# Better_Flasher.net
KiCad netlist of a schematic drawn in EAGLE
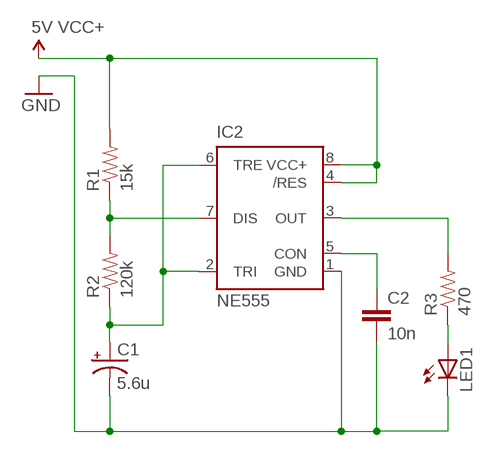
[diagram p0: schematic, sheet 1]

(export (version "E")
  (design (tool "Eeschema 10.0.6"))
  (components
    (comp (ref "C1")
      (value "5.6u")
      (footprint "eagle-import:CPOL-RADIAL-10UF-25V")
      (libsource (lib "eagle-import") (part "CAP_POLPTH2"))
    )
    (comp (ref "C2")
      (value "10n")
      (footprint "eagle-import:CAP-PTH-SMALL")
      (libsource (lib "eagle-import") (part "CAPPTH"))
    )
    (comp (ref "IC2")
      (value "NE555")
      (footprint "eagle-import:DIL-08")
      (fields (field (name "MF") "Arrow Electronics") (field (name "MPN") "NE555N"))
      (libsource (lib "eagle-import") (part "NE555"))
    )
    (comp (ref "LED1")
      (value "LED5MM")
      (footprint "eagle-import:LED5MM")
      (libsource (lib "eagle-import") (part "LED5MM"))
    )
    (comp (ref "R1")
      (value "15k")
      (footprint "eagle-import:AXIAL-0.3")
      (libsource (lib "eagle-import") (part "RESISTORAXIAL-0.3"))
    )
    (comp (ref "R2")
      (value "120k")
      (footprint "eagle-import:AXIAL-0.3")
      (libsource (lib "eagle-import") (part "RESISTORAXIAL-0.3"))
    )
    (comp (ref "R3")
      (value "470")
      (footprint "eagle-import:AXIAL-0.3")
      (libsource (lib "eagle-import") (part "RESISTORAXIAL-0.3"))
    )
  )
  (nets
    (net (code "1") (name "5V VCC+") (class "Default")
      (node (ref "IC2") (pin "4") (pinfunction "/RES_4") (pintype "input"))
      (node (ref "IC2") (pin "8") (pinfunction "VCC+_8") (pintype "power_in"))
      (node (ref "R1") (pin "P$2") (pinfunction "2_P$2") (pintype "passive"))
    )
    (net (code "2") (name "GND") (class "Default")
      (node (ref "C1") (pin "2") (pinfunction "-_2") (pintype "passive"))
      (node (ref "C2") (pin "2") (pinfunction "2_2") (pintype "passive"))
      (node (ref "IC2") (pin "1") (pinfunction "GND_1") (pintype "power_in"))
      (node (ref "LED1") (pin "K") (pinfunction "C_K") (pintype "passive"))
    )
    (net (code "3") (name "Net-(C1-+)") (class "Default")
      (node (ref "C1") (pin "1") (pinfunction "+_1") (pintype "passive"))
      (node (ref "IC2") (pin "2") (pinfunction "TRI_2") (pintype "input"))
      (node (ref "IC2") (pin "6") (pinfunction "TRE_6") (pintype "input"))
      (node (ref "R2") (pin "P$1") (pinfunction "1_P$1") (pintype "passive"))
    )
    (net (code "4") (name "Net-(IC2-CON)") (class "Default")
      (node (ref "C2") (pin "1") (pinfunction "1_1") (pintype "passive"))
      (node (ref "IC2") (pin "5") (pinfunction "CON_5") (pintype "input"))
    )
    (net (code "5") (name "Net-(IC2-DIS)") (class "Default")
      (node (ref "IC2") (pin "7") (pinfunction "DIS_7") (pintype "input"))
      (node (ref "R1") (pin "P$1") (pinfunction "1_P$1") (pintype "passive"))
      (node (ref "R2") (pin "P$2") (pinfunction "2_P$2") (pintype "passive"))
    )
    (net (code "6") (name "Net-(IC2-OUT)") (class "Default")
      (node (ref "IC2") (pin "3") (pinfunction "OUT_3") (pintype "output"))
      (node (ref "R3") (pin "P$2") (pinfunction "2_P$2") (pintype "passive"))
    )
    (net (code "7") (name "Net-(R3-1)") (class "Default")
      (node (ref "LED1") (pin "A") (pinfunction "A_A") (pintype "passive"))
      (node (ref "R3") (pin "P$1") (pinfunction "1_P$1") (pintype "passive"))
    )
  )
)
